# Schematic.net
KiCad netlist of a schematic drawn in EAGLE
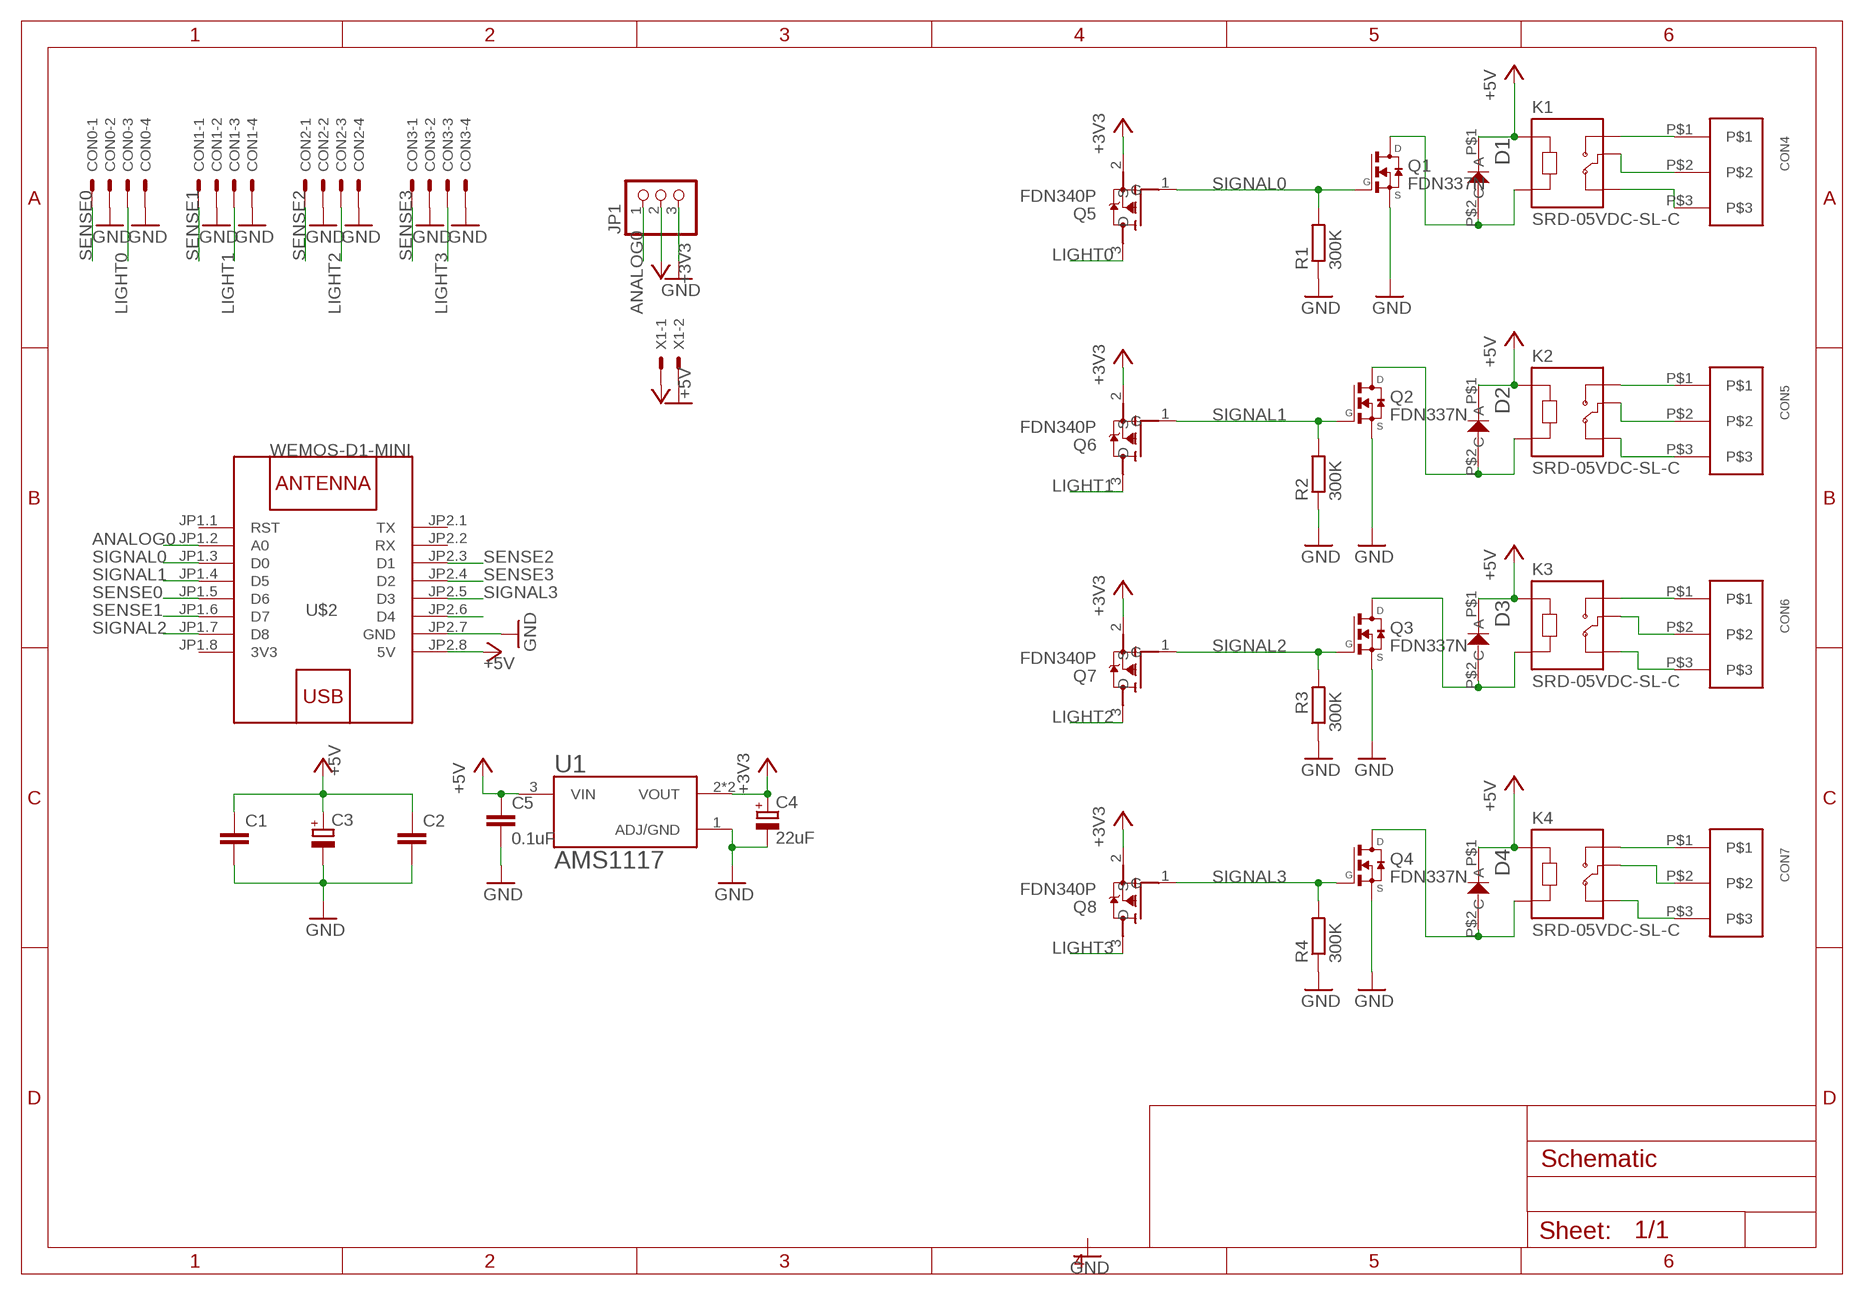
[diagram p0: schematic, sheet 1]

(export (version "E")
  (design (tool "Eeschema 10.0.6"))
  (components
    (comp (ref "C1")
      (value "C-EUC0603")
      (footprint "eagle-import:C0603")
      (libsource (lib "eagle-import") (part "C-EUC0603"))
    )
    (comp (ref "C2")
      (value "C-EUC0603")
      (footprint "eagle-import:C0603")
      (libsource (lib "eagle-import") (part "C-EUC0603"))
    )
    (comp (ref "C3")
      (value "CPOL-EUB")
      (footprint "eagle-import:PANASONIC_B")
      (libsource (lib "eagle-import") (part "CPOL-EUB"))
    )
    (comp (ref "C4")
      (value "22uF")
      (footprint "eagle-import:C_6032-28R")
      (libsource (lib "eagle-import") (part "CPOL-EUC/6032-28R"))
    )
    (comp (ref "C5")
      (value "0.1uF")
      (footprint "eagle-import:C0603")
      (libsource (lib "eagle-import") (part "C-EUC0603"))
    )
    (comp (ref "CON0")
      (value "JST-XH-04-PIN-LONG-PAD")
      (footprint "eagle-import:JST-XH-04-PACKAGE-LONG-PAD")
      (libsource (lib "eagle-import") (part "JST-XH-04-PIN-LONG-PAD"))
    )
    (comp (ref "CON1")
      (value "JST-XH-04-PIN-LONG-PAD")
      (footprint "eagle-import:JST-XH-04-PACKAGE-LONG-PAD")
      (libsource (lib "eagle-import") (part "JST-XH-04-PIN-LONG-PAD"))
    )
    (comp (ref "CON2")
      (value "JST-XH-04-PIN-LONG-PAD")
      (footprint "eagle-import:JST-XH-04-PACKAGE-LONG-PAD")
      (libsource (lib "eagle-import") (part "JST-XH-04-PIN-LONG-PAD"))
    )
    (comp (ref "CON3")
      (value "JST-XH-04-PIN-LONG-PAD")
      (footprint "eagle-import:JST-XH-04-PACKAGE-LONG-PAD")
      (libsource (lib "eagle-import") (part "JST-XH-04-PIN-LONG-PAD"))
    )
    (comp (ref "CON4")
      (value "KF-301-3P")
      (footprint "eagle-import:STD")
      (libsource (lib "eagle-import") (part "KF-301-3P"))
    )
    (comp (ref "CON5")
      (value "KF-301-3P")
      (footprint "eagle-import:STD")
      (libsource (lib "eagle-import") (part "KF-301-3P"))
    )
    (comp (ref "CON6")
      (value "KF-301-3P")
      (footprint "eagle-import:STD")
      (libsource (lib "eagle-import") (part "KF-301-3P"))
    )
    (comp (ref "CON7")
      (value "KF-301-3P")
      (footprint "eagle-import:STD")
      (libsource (lib "eagle-import") (part "KF-301-3P"))
    )
    (comp (ref "D1") (value "M7") (footprint "eagle-import:M7") (libsource (lib "eagle-import") (part "M7")))
    (comp (ref "D2") (value "M7") (footprint "eagle-import:M7") (libsource (lib "eagle-import") (part "M7")))
    (comp (ref "D3") (value "M7") (footprint "eagle-import:M7") (libsource (lib "eagle-import") (part "M7")))
    (comp (ref "D4") (value "M7") (footprint "eagle-import:M7") (libsource (lib "eagle-import") (part "M7")))
    (comp (ref "JP1")
      (value "PINHD-1X3")
      (footprint "eagle-import:1X03")
      (libsource (lib "eagle-import") (part "PINHD-1X3"))
    )
    (comp (ref "K1")
      (value "SRD-05VDC-SL-C")
      (footprint "eagle-import:RELAY_SRD-05VDC-SL-C")
      (fields (field (name "MF") "Songle Relay"))
      (libsource (lib "eagle-import") (part "SRD-05VDC-SL-C"))
    )
    (comp (ref "K2")
      (value "SRD-05VDC-SL-C")
      (footprint "eagle-import:RELAY_SRD-05VDC-SL-C")
      (fields (field (name "MF") "Songle Relay"))
      (libsource (lib "eagle-import") (part "SRD-05VDC-SL-C"))
    )
    (comp (ref "K3")
      (value "SRD-05VDC-SL-C")
      (footprint "eagle-import:RELAY_SRD-05VDC-SL-C")
      (fields (field (name "MF") "Songle Relay"))
      (libsource (lib "eagle-import") (part "SRD-05VDC-SL-C"))
    )
    (comp (ref "K4")
      (value "SRD-05VDC-SL-C")
      (footprint "eagle-import:RELAY_SRD-05VDC-SL-C")
      (fields (field (name "MF") "Songle Relay"))
      (libsource (lib "eagle-import") (part "SRD-05VDC-SL-C"))
    )
    (comp (ref "Q1")
      (value "FDN337N")
      (footprint "eagle-import:SSOT-3")
      (fields (field (name "MF") "ON Semiconductor"))
      (libsource (lib "eagle-import") (part "FDN337N"))
    )
    (comp (ref "Q2")
      (value "FDN337N")
      (footprint "eagle-import:SSOT-3")
      (fields (field (name "MF") "ON Semiconductor"))
      (libsource (lib "eagle-import") (part "FDN337N"))
    )
    (comp (ref "Q3")
      (value "FDN337N")
      (footprint "eagle-import:SSOT-3")
      (fields (field (name "MF") "ON Semiconductor"))
      (libsource (lib "eagle-import") (part "FDN337N"))
    )
    (comp (ref "Q4")
      (value "FDN337N")
      (footprint "eagle-import:SSOT-3")
      (fields (field (name "MF") "ON Semiconductor"))
      (libsource (lib "eagle-import") (part "FDN337N"))
    )
    (comp (ref "Q5")
      (value "FDN340P")
      (footprint "eagle-import:SOT95P240X120-3N")
      (fields (field (name "MF") "ON Semiconductor"))
      (libsource (lib "eagle-import") (part "FDN340P"))
    )
    (comp (ref "Q6")
      (value "FDN340P")
      (footprint "eagle-import:SOT95P240X120-3N")
      (fields (field (name "MF") "ON Semiconductor"))
      (libsource (lib "eagle-import") (part "FDN340P"))
    )
    (comp (ref "Q7")
      (value "FDN340P")
      (footprint "eagle-import:SOT95P240X120-3N")
      (fields (field (name "MF") "ON Semiconductor"))
      (libsource (lib "eagle-import") (part "FDN340P"))
    )
    (comp (ref "Q8")
      (value "FDN340P")
      (footprint "eagle-import:SOT95P240X120-3N")
      (fields (field (name "MF") "ON Semiconductor"))
      (libsource (lib "eagle-import") (part "FDN340P"))
    )
    (comp (ref "R1")
      (value "300K")
      (footprint "eagle-import:R1206")
      (libsource (lib "eagle-import") (part "R-EU_R1206"))
    )
    (comp (ref "R2")
      (value "300K")
      (footprint "eagle-import:R1206")
      (libsource (lib "eagle-import") (part "R-EU_R1206"))
    )
    (comp (ref "R3")
      (value "300K")
      (footprint "eagle-import:R1206")
      (libsource (lib "eagle-import") (part "R-EU_R1206"))
    )
    (comp (ref "R4")
      (value "300K")
      (footprint "eagle-import:R1206")
      (libsource (lib "eagle-import") (part "R-EU_R1206"))
    )
    (comp (ref "U$2")
      (value "WEMOS-D1-MINI")
      (footprint "eagle-import:WEMOS-D1-MINI")
      (libsource (lib "eagle-import") (part "WEMOS-D1-MINI"))
    )
    (comp (ref "U1")
      (value "AMS1117")
      (footprint "eagle-import:SOT229P700X180-4N")
      (fields (field (name "MF") "Advanced Monolithic Systems"))
      (libsource (lib "eagle-import") (part "AMS1117"))
    )
    (comp (ref "X1")
      (value "JST-XH-02-PIN-LONG-PAD")
      (footprint "eagle-import:JST-XH-02-PACKAGE-LONG-PAD")
      (libsource (lib "eagle-import") (part "JST-XH-02-PIN-LONG-PAD"))
    )
  )
  (nets
    (net (code "1") (name "+3V3") (class "Default")
      (node (ref "C4") (pin "+") (pinfunction "+_+") (pintype "passive"))
      (node (ref "JP1") (pin "2") (pinfunction "2_2") (pintype "passive"))
      (node (ref "Q5") (pin "2") (pinfunction "S_2") (pintype "passive"))
      (node (ref "Q6") (pin "2") (pinfunction "S_2") (pintype "passive"))
      (node (ref "Q7") (pin "2") (pinfunction "S_2") (pintype "passive"))
      (node (ref "Q8") (pin "2") (pinfunction "S_2") (pintype "passive"))
      (node (ref "U1") (pin "2") (pinfunction "VOUT_2") (pintype "output"))
      (node (ref "U1") (pin "4") (pinfunction "VOUT_4") (pintype "output"))
    )
    (net (code "2") (name "+5V") (class "Default")
      (node (ref "C1") (pin "1") (pinfunction "1_1") (pintype "passive"))
      (node (ref "C2") (pin "1") (pinfunction "1_1") (pintype "passive"))
      (node (ref "C3") (pin "+") (pinfunction "+_+") (pintype "passive"))
      (node (ref "C5") (pin "1") (pinfunction "1_1") (pintype "passive"))
      (node (ref "D1") (pin "P$1") (pinfunction "C_P$1") (pintype "bidirectional"))
      (node (ref "D2") (pin "P$1") (pinfunction "C_P$1") (pintype "bidirectional"))
      (node (ref "D3") (pin "P$1") (pinfunction "C_P$1") (pintype "bidirectional"))
      (node (ref "D4") (pin "P$1") (pinfunction "C_P$1") (pintype "bidirectional"))
      (node (ref "K1") (pin "A1") (pinfunction "A1_A1") (pintype "passive"))
      (node (ref "K2") (pin "A1") (pinfunction "A1_A1") (pintype "passive"))
      (node (ref "K3") (pin "A1") (pinfunction "A1_A1") (pintype "passive"))
      (node (ref "K4") (pin "A1") (pinfunction "A1_A1") (pintype "passive"))
      (node (ref "U$2") (pin "JP2.8") (pinfunction "5V_JP2.8") (pintype "power_in"))
      (node (ref "U1") (pin "3") (pinfunction "VIN_3") (pintype "input"))
      (node (ref "X1") (pin "1") (pinfunction "S_1") (pintype "passive"))
    )
    (net (code "3") (name "/3V3") (class "Default")
      (node (ref "U$2") (pin "JP1.8") (pinfunction "3V3_JP1.8") (pintype "power_in"))
    )
    (net (code "4") (name "/ANALOG0") (class "Default")
      (node (ref "JP1") (pin "1") (pinfunction "1_1") (pintype "passive"))
      (node (ref "U$2") (pin "JP1.2") (pinfunction "A0_JP1.2") (pintype "bidirectional"))
    )
    (net (code "5") (name "/LIGHT0") (class "Default")
      (node (ref "CON0") (pin "3") (pinfunction "S_3") (pintype "passive"))
      (node (ref "Q5") (pin "3") (pinfunction "D_3") (pintype "passive"))
    )
    (net (code "6") (name "/LIGHT1") (class "Default")
      (node (ref "CON1") (pin "3") (pinfunction "S_3") (pintype "passive"))
      (node (ref "Q6") (pin "3") (pinfunction "D_3") (pintype "passive"))
    )
    (net (code "7") (name "/LIGHT2") (class "Default")
      (node (ref "CON2") (pin "3") (pinfunction "S_3") (pintype "passive"))
      (node (ref "Q7") (pin "3") (pinfunction "D_3") (pintype "passive"))
    )
    (net (code "8") (name "/LIGHT3") (class "Default")
      (node (ref "CON3") (pin "3") (pinfunction "S_3") (pintype "passive"))
      (node (ref "Q8") (pin "3") (pinfunction "D_3") (pintype "passive"))
    )
    (net (code "9") (name "/SENSE0") (class "Default")
      (node (ref "CON0") (pin "1") (pinfunction "S_1") (pintype "passive"))
      (node (ref "U$2") (pin "JP1.5") (pinfunction "D6_JP1.5") (pintype "bidirectional"))
    )
    (net (code "10") (name "/SENSE1") (class "Default")
      (node (ref "CON1") (pin "1") (pinfunction "S_1") (pintype "passive"))
      (node (ref "U$2") (pin "JP1.6") (pinfunction "D7_JP1.6") (pintype "bidirectional"))
    )
    (net (code "11") (name "/SENSE2") (class "Default")
      (node (ref "CON2") (pin "1") (pinfunction "S_1") (pintype "passive"))
      (node (ref "U$2") (pin "JP2.3") (pinfunction "D1_JP2.3") (pintype "bidirectional"))
    )
    (net (code "12") (name "/SENSE3") (class "Default")
      (node (ref "CON3") (pin "1") (pinfunction "S_1") (pintype "passive"))
      (node (ref "U$2") (pin "JP2.4") (pinfunction "D2_JP2.4") (pintype "bidirectional"))
    )
    (net (code "13") (name "/SIGNAL0") (class "Default")
      (node (ref "Q1") (pin "1") (pinfunction "G_1") (pintype "passive"))
      (node (ref "Q5") (pin "1") (pinfunction "G_1") (pintype "passive"))
      (node (ref "R1") (pin "2") (pinfunction "2_2") (pintype "passive"))
      (node (ref "U$2") (pin "JP1.3") (pinfunction "D0_JP1.3") (pintype "bidirectional"))
    )
    (net (code "14") (name "/SIGNAL1") (class "Default")
      (node (ref "Q2") (pin "1") (pinfunction "G_1") (pintype "passive"))
      (node (ref "Q6") (pin "1") (pinfunction "G_1") (pintype "passive"))
      (node (ref "R2") (pin "2") (pinfunction "2_2") (pintype "passive"))
      (node (ref "U$2") (pin "JP1.4") (pinfunction "D5_JP1.4") (pintype "bidirectional"))
    )
    (net (code "15") (name "/SIGNAL2") (class "Default")
      (node (ref "Q3") (pin "1") (pinfunction "G_1") (pintype "passive"))
      (node (ref "Q7") (pin "1") (pinfunction "G_1") (pintype "passive"))
      (node (ref "R3") (pin "2") (pinfunction "2_2") (pintype "passive"))
      (node (ref "U$2") (pin "JP1.7") (pinfunction "D8_JP1.7") (pintype "bidirectional"))
    )
    (net (code "16") (name "/SIGNAL3") (class "Default")
      (node (ref "Q4") (pin "1") (pinfunction "G_1") (pintype "passive"))
      (node (ref "Q8") (pin "1") (pinfunction "G_1") (pintype "passive"))
      (node (ref "R4") (pin "2") (pinfunction "2_2") (pintype "passive"))
      (node (ref "U$2") (pin "JP2.5") (pinfunction "D3_JP2.5") (pintype "bidirectional"))
    )
    (net (code "17") (name "GND") (class "Default")
      (node (ref "C1") (pin "2") (pinfunction "2_2") (pintype "passive"))
      (node (ref "C2") (pin "2") (pinfunction "2_2") (pintype "passive"))
      (node (ref "C3") (pin "-") (pinfunction "-_-") (pintype "passive"))
      (node (ref "C4") (pin "-") (pinfunction "-_-") (pintype "passive"))
      (node (ref "C5") (pin "2") (pinfunction "2_2") (pintype "passive"))
      (node (ref "CON0") (pin "2") (pinfunction "S_2") (pintype "passive"))
      (node (ref "CON0") (pin "4") (pinfunction "S_4") (pintype "passive"))
      (node (ref "CON1") (pin "2") (pinfunction "S_2") (pintype "passive"))
      (node (ref "CON1") (pin "4") (pinfunction "S_4") (pintype "passive"))
      (node (ref "CON2") (pin "2") (pinfunction "S_2") (pintype "passive"))
      (node (ref "CON2") (pin "4") (pinfunction "S_4") (pintype "passive"))
      (node (ref "CON3") (pin "2") (pinfunction "S_2") (pintype "passive"))
      (node (ref "CON3") (pin "4") (pinfunction "S_4") (pintype "passive"))
      (node (ref "JP1") (pin "3") (pinfunction "3_3") (pintype "passive"))
      (node (ref "Q1") (pin "2") (pinfunction "S_2") (pintype "passive"))
      (node (ref "Q2") (pin "2") (pinfunction "S_2") (pintype "passive"))
      (node (ref "Q3") (pin "2") (pinfunction "S_2") (pintype "passive"))
      (node (ref "Q4") (pin "2") (pinfunction "S_2") (pintype "passive"))
      (node (ref "R1") (pin "1") (pinfunction "1_1") (pintype "passive"))
      (node (ref "R2") (pin "1") (pinfunction "1_1") (pintype "passive"))
      (node (ref "R3") (pin "1") (pinfunction "1_1") (pintype "passive"))
      (node (ref "R4") (pin "1") (pinfunction "1_1") (pintype "passive"))
      (node (ref "U$2") (pin "JP2.7") (pinfunction "GND_JP2.7") (pintype "power_in"))
      (node (ref "U1") (pin "1") (pinfunction "ADJ/GND_1") (pintype "power_in"))
      (node (ref "X1") (pin "2") (pinfunction "S_2") (pintype "passive"))
    )
    (net (code "18") (name "Net-(CON4-PadP$1)") (class "Default")
      (node (ref "CON4") (pin "P$1") (pinfunction "P$1_P$1") (pintype "bidirectional"))
      (node (ref "K1") (pin "NO") (pinfunction "NO_NO") (pintype "passive"))
    )
    (net (code "19") (name "Net-(CON4-PadP$2)") (class "Default")
      (node (ref "CON4") (pin "P$2") (pinfunction "P$2_P$2") (pintype "bidirectional"))
      (node (ref "K1") (pin "COM") (pinfunction "COM_COM") (pintype "passive"))
    )
    (net (code "20") (name "Net-(CON4-PadP$3)") (class "Default")
      (node (ref "CON4") (pin "P$3") (pinfunction "P$3_P$3") (pintype "bidirectional"))
      (node (ref "K1") (pin "NC") (pinfunction "NC_NC") (pintype "passive"))
    )
    (net (code "21") (name "Net-(CON5-PadP$1)") (class "Default")
      (node (ref "CON5") (pin "P$1") (pinfunction "P$1_P$1") (pintype "bidirectional"))
      (node (ref "K2") (pin "NO") (pinfunction "NO_NO") (pintype "passive"))
    )
    (net (code "22") (name "Net-(CON5-PadP$2)") (class "Default")
      (node (ref "CON5") (pin "P$2") (pinfunction "P$2_P$2") (pintype "bidirectional"))
      (node (ref "K2") (pin "COM") (pinfunction "COM_COM") (pintype "passive"))
    )
    (net (code "23") (name "Net-(CON5-PadP$3)") (class "Default")
      (node (ref "CON5") (pin "P$3") (pinfunction "P$3_P$3") (pintype "bidirectional"))
      (node (ref "K2") (pin "NC") (pinfunction "NC_NC") (pintype "passive"))
    )
    (net (code "24") (name "Net-(CON6-PadP$1)") (class "Default")
      (node (ref "CON6") (pin "P$1") (pinfunction "P$1_P$1") (pintype "bidirectional"))
      (node (ref "K3") (pin "NO") (pinfunction "NO_NO") (pintype "passive"))
    )
    (net (code "25") (name "Net-(CON6-PadP$2)") (class "Default")
      (node (ref "CON6") (pin "P$2") (pinfunction "P$2_P$2") (pintype "bidirectional"))
      (node (ref "K3") (pin "COM") (pinfunction "COM_COM") (pintype "passive"))
    )
    (net (code "26") (name "Net-(CON6-PadP$3)") (class "Default")
      (node (ref "CON6") (pin "P$3") (pinfunction "P$3_P$3") (pintype "bidirectional"))
      (node (ref "K3") (pin "NC") (pinfunction "NC_NC") (pintype "passive"))
    )
    (net (code "27") (name "Net-(CON7-PadP$1)") (class "Default")
      (node (ref "CON7") (pin "P$1") (pinfunction "P$1_P$1") (pintype "bidirectional"))
      (node (ref "K4") (pin "NO") (pinfunction "NO_NO") (pintype "passive"))
    )
    (net (code "28") (name "Net-(CON7-PadP$2)") (class "Default")
      (node (ref "CON7") (pin "P$2") (pinfunction "P$2_P$2") (pintype "bidirectional"))
      (node (ref "K4") (pin "COM") (pinfunction "COM_COM") (pintype "passive"))
    )
    (net (code "29") (name "Net-(CON7-PadP$3)") (class "Default")
      (node (ref "CON7") (pin "P$3") (pinfunction "P$3_P$3") (pintype "bidirectional"))
      (node (ref "K4") (pin "NC") (pinfunction "NC_NC") (pintype "passive"))
    )
    (net (code "30") (name "Net-(D1-A)") (class "Default")
      (node (ref "D1") (pin "P$2") (pinfunction "A_P$2") (pintype "bidirectional"))
      (node (ref "K1") (pin "A2") (pinfunction "A2_A2") (pintype "passive"))
      (node (ref "Q1") (pin "3") (pinfunction "D_3") (pintype "passive"))
    )
    (net (code "31") (name "Net-(D2-A)") (class "Default")
      (node (ref "D2") (pin "P$2") (pinfunction "A_P$2") (pintype "bidirectional"))
      (node (ref "K2") (pin "A2") (pinfunction "A2_A2") (pintype "passive"))
      (node (ref "Q2") (pin "3") (pinfunction "D_3") (pintype "passive"))
    )
    (net (code "32") (name "Net-(D3-A)") (class "Default")
      (node (ref "D3") (pin "P$2") (pinfunction "A_P$2") (pintype "bidirectional"))
      (node (ref "K3") (pin "A2") (pinfunction "A2_A2") (pintype "passive"))
      (node (ref "Q3") (pin "3") (pinfunction "D_3") (pintype "passive"))
    )
    (net (code "33") (name "Net-(D4-A)") (class "Default")
      (node (ref "D4") (pin "P$2") (pinfunction "A_P$2") (pintype "bidirectional"))
      (node (ref "K4") (pin "A2") (pinfunction "A2_A2") (pintype "passive"))
      (node (ref "Q4") (pin "3") (pinfunction "D_3") (pintype "passive"))
    )
    (net (code "34") (name "unconnected-(U$2-D4-PadJP2.6)") (class "Default")
      (node (ref "U$2") (pin "JP2.6") (pinfunction "D4_JP2.6") (pintype "bidirectional"))
    )
    (net (code "35") (name "unconnected-(U$2-RST-PadJP1.1)") (class "Default")
      (node (ref "U$2") (pin "JP1.1") (pinfunction "RST_JP1.1") (pintype "bidirectional"))
    )
    (net (code "36") (name "unconnected-(U$2-RX-PadJP2.2)") (class "Default")
      (node (ref "U$2") (pin "JP2.2") (pinfunction "RX_JP2.2") (pintype "bidirectional"))
    )
    (net (code "37") (name "unconnected-(U$2-TX-PadJP2.1)") (class "Default")
      (node (ref "U$2") (pin "JP2.1") (pinfunction "TX_JP2.1") (pintype "bidirectional"))
    )
  )
)
